# esd_fall_project_rev1.net
KiCad netlist of a schematic drawn in EAGLE
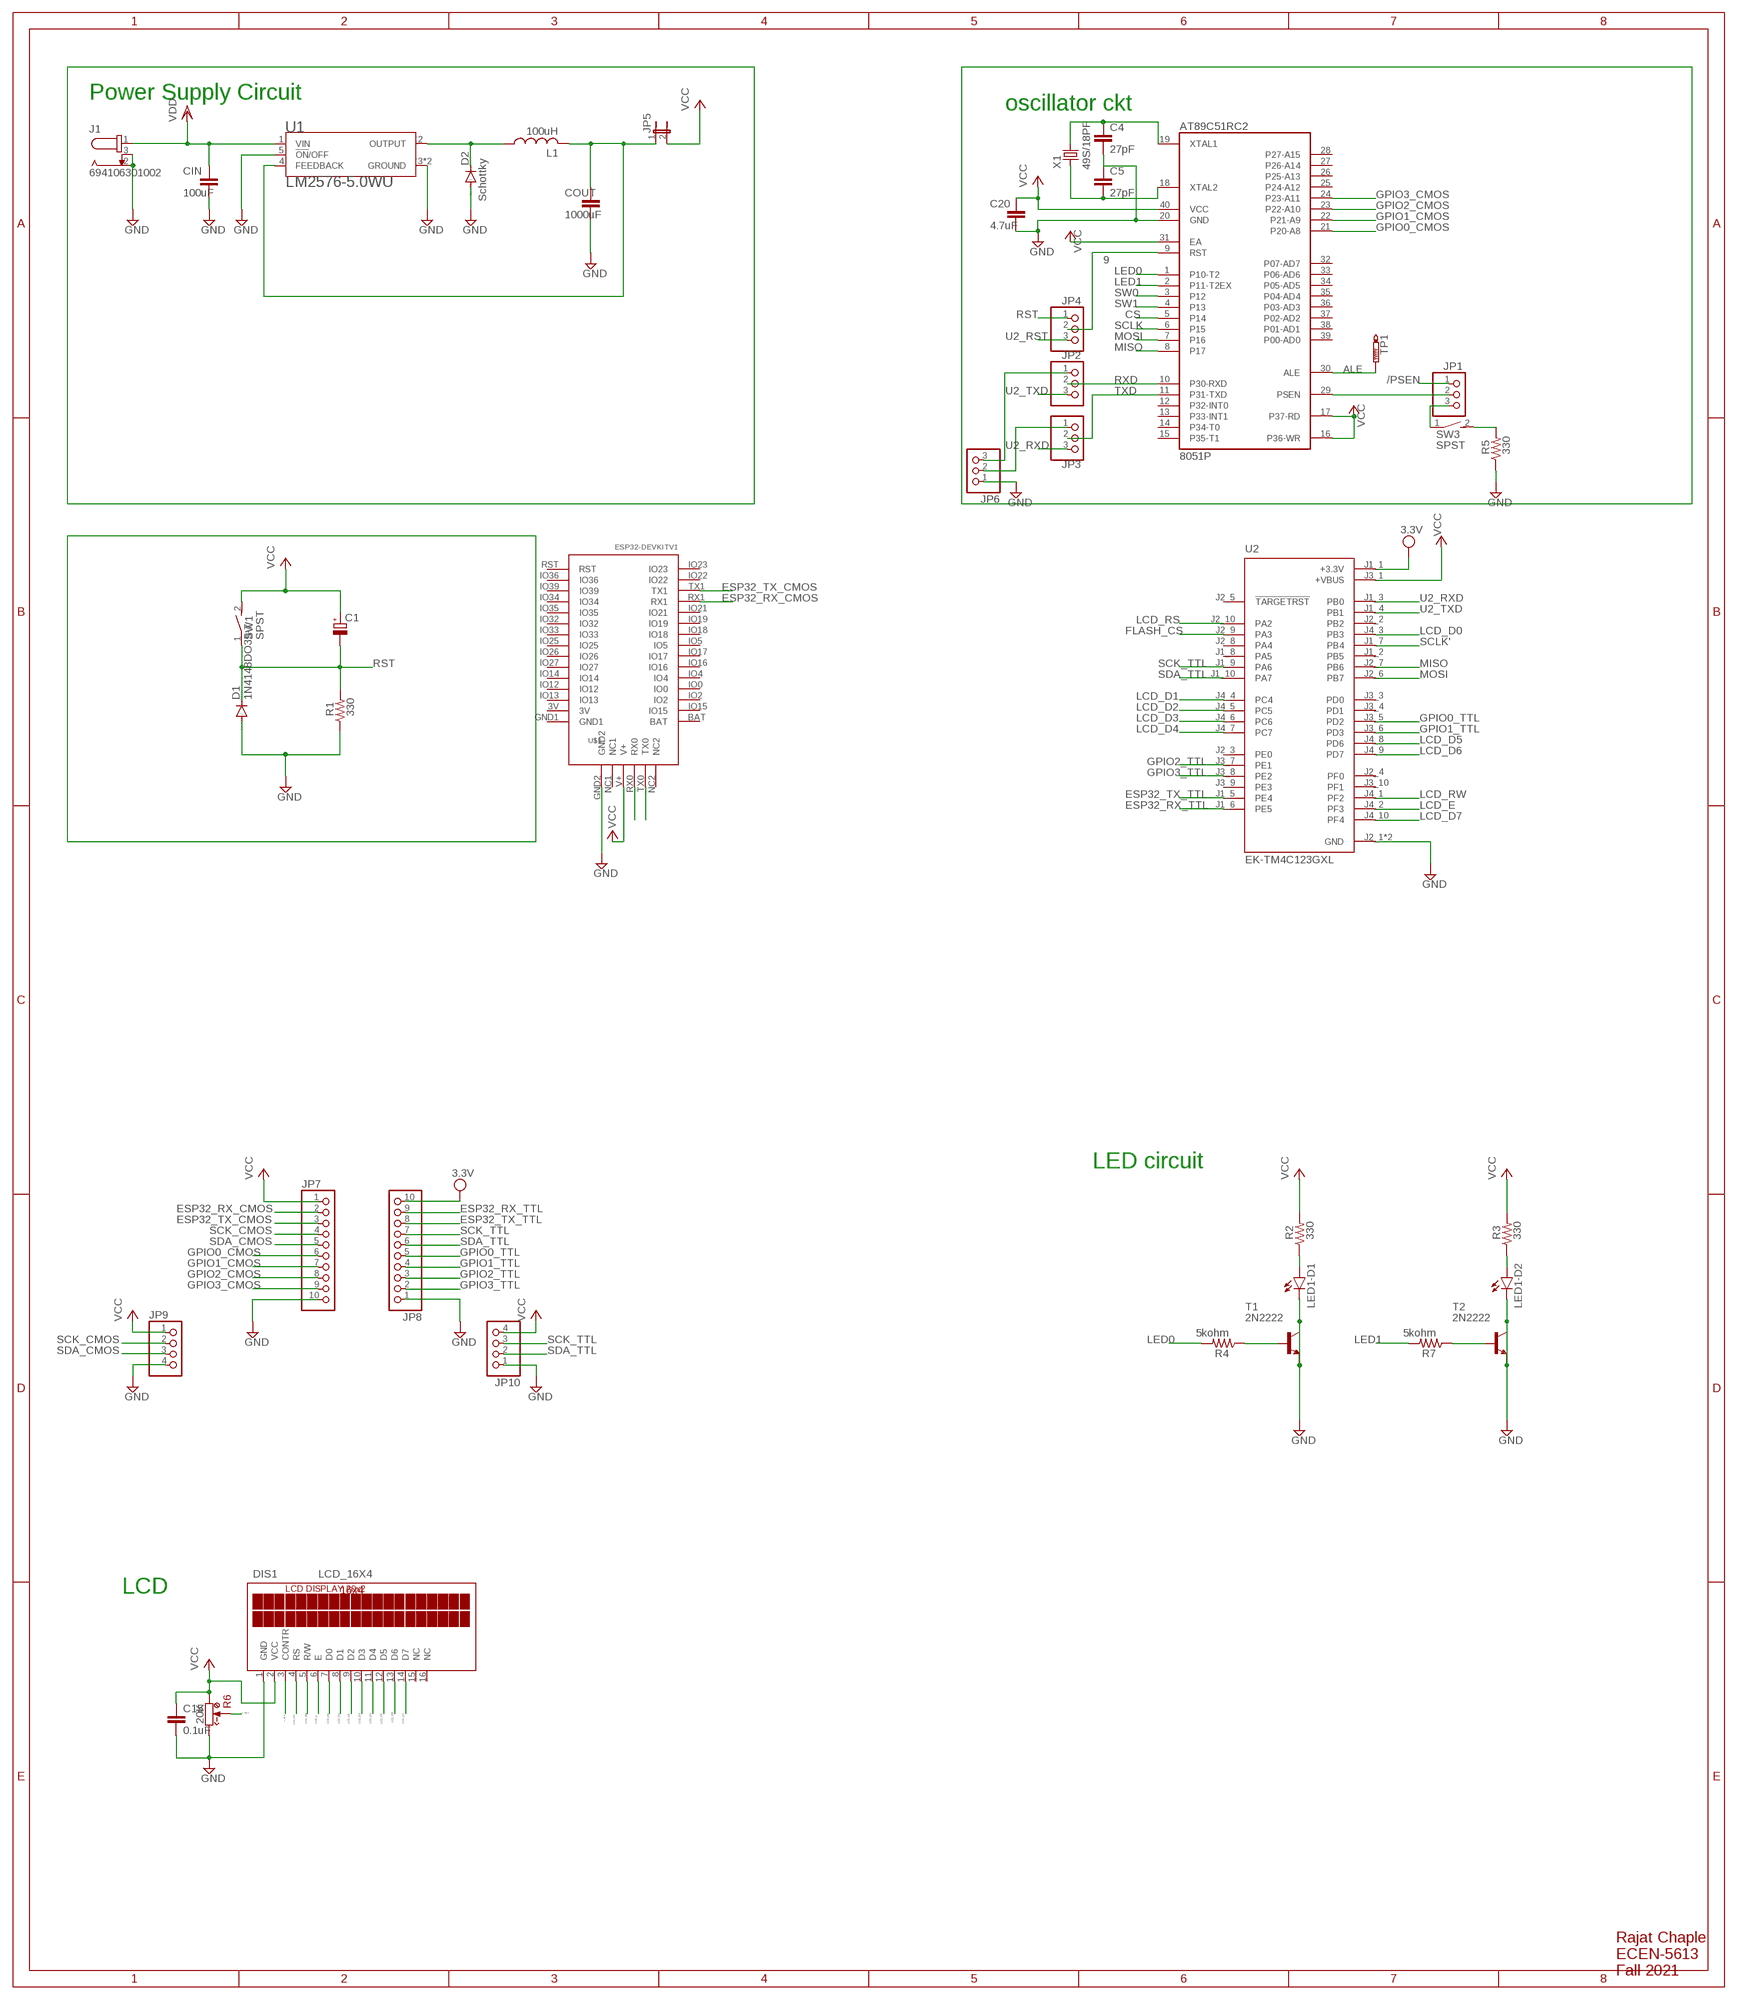
[diagram p0: schematic, sheet 1]

(export (version "E")
  (design (tool "Eeschema 10.0.6"))
  (components
    (comp (ref "AT89C51RC2")
      (value "8051P")
      (footprint "eagle-import:DIL40")
      (libsource (lib "eagle-import") (part "8051P"))
    )
    (comp (ref "C1")
      (value "CPOL-EUE1.8-4")
      (footprint "eagle-import:E1,8-4")
      (libsource (lib "eagle-import") (part "CPOL-EUE1.8-4"))
    )
    (comp (ref "C4")
      (value "27pF")
      (footprint "eagle-import:C2.5-3")
      (libsource (lib "eagle-import") (part "C2,5-3"))
    )
    (comp (ref "C5")
      (value "27pF")
      (footprint "eagle-import:C2.5-3")
      (libsource (lib "eagle-import") (part "C2,5-3"))
    )
    (comp (ref "C15")
      (value "0.1uF")
      (footprint "eagle-import:C2.5-3")
      (libsource (lib "eagle-import") (part "C2,5-3"))
    )
    (comp (ref "C20")
      (value "4.7uF")
      (footprint "eagle-import:C2.5-3")
      (libsource (lib "eagle-import") (part "C2,5-3"))
    )
    (comp (ref "CIN")
      (value "100uF")
      (footprint "eagle-import:C2.5-3")
      (libsource (lib "eagle-import") (part "C2,5-3"))
    )
    (comp (ref "COUT")
      (value "1000uF")
      (footprint "eagle-import:C2.5-3")
      (libsource (lib "eagle-import") (part "C2,5-3"))
    )
    (comp (ref "D1")
      (value "1N4148DO35-7")
      (footprint "eagle-import:DO35-7")
      (libsource (lib "eagle-import") (part "1N4148DO35-7"))
    )
    (comp (ref "D2")
      (value "Schottky")
      (footprint "eagle-import:DO35-7")
      (libsource (lib "eagle-import") (part "1N4148DO35-7"))
    )
    (comp (ref "DIS1")
      (value "LCD_16X4")
      (footprint "eagle-import:TUXGR_20X2")
      (libsource (lib "eagle-import") (part "TUXGR_20X2"))
    )
    (comp (ref "J1")
      (value "694106301002")
      (footprint "eagle-import:694106301002")
      (fields
        (field (name "DIGIKEY_PART_NUMBER") "732-5930-ND")
        (field (name "MANUFACTURER") "Wurth Electronics Inc.")
        (field (name "CREATED_BY") "PCBLayout.com")
      )
      (libsource (lib "eagle-import") (part "694106301002"))
    )
    (comp (ref "JP1")
      (value "PINHD-1X3")
      (footprint "eagle-import:1X03")
      (libsource (lib "eagle-import") (part "PINHD-1X3"))
    )
    (comp (ref "JP2")
      (value "PINHD-1X3")
      (footprint "eagle-import:1X03")
      (libsource (lib "eagle-import") (part "PINHD-1X3"))
    )
    (comp (ref "JP3")
      (value "PINHD-1X3")
      (footprint "eagle-import:1X03")
      (libsource (lib "eagle-import") (part "PINHD-1X3"))
    )
    (comp (ref "JP4")
      (value "PINHD-1X3")
      (footprint "eagle-import:1X03")
      (libsource (lib "eagle-import") (part "PINHD-1X3"))
    )
    (comp (ref "JP5")
      (value "JP1E")
      (footprint "eagle-import:JP1")
      (libsource (lib "eagle-import") (part "JP1E"))
    )
    (comp (ref "JP6")
      (value "PINHD-1X3")
      (footprint "eagle-import:1X03")
      (libsource (lib "eagle-import") (part "PINHD-1X3"))
    )
    (comp (ref "JP7")
      (value "PINHD-1X10")
      (footprint "eagle-import:1X10")
      (libsource (lib "eagle-import") (part "PINHD-1X10"))
    )
    (comp (ref "JP8")
      (value "PINHD-1X10")
      (footprint "eagle-import:1X10")
      (libsource (lib "eagle-import") (part "PINHD-1X10"))
    )
    (comp (ref "JP9")
      (value "PINHD-1X4")
      (footprint "eagle-import:1X04")
      (libsource (lib "eagle-import") (part "PINHD-1X4"))
    )
    (comp (ref "JP10")
      (value "PINHD-1X4")
      (footprint "eagle-import:1X04")
      (libsource (lib "eagle-import") (part "PINHD-1X4"))
    )
    (comp (ref "L1")
      (value "100uH")
      (footprint "eagle-import:0204_5")
      (libsource (lib "eagle-import") (part "L-US0204/5"))
    )
    (comp (ref "LED1-D1")
      (value "LED5MM")
      (footprint "eagle-import:LED5MM")
      (libsource (lib "eagle-import") (part "LED5MM"))
    )
    (comp (ref "LED1-D2")
      (value "LED5MM")
      (footprint "eagle-import:LED5MM")
      (libsource (lib "eagle-import") (part "LED5MM"))
    )
    (comp (ref "R1")
      (value "330")
      (footprint "eagle-import:0204_7")
      (libsource (lib "eagle-import") (part "R-US_0204/7"))
    )
    (comp (ref "R2")
      (value "330")
      (footprint "eagle-import:0204_7")
      (libsource (lib "eagle-import") (part "R-US_0204/7"))
    )
    (comp (ref "R3")
      (value "330")
      (footprint "eagle-import:0204_7")
      (libsource (lib "eagle-import") (part "R-US_0204/7"))
    )
    (comp (ref "R4")
      (value "5kohm")
      (footprint "eagle-import:0204_7")
      (libsource (lib "eagle-import") (part "R-US_0204/7"))
    )
    (comp (ref "R5")
      (value "330")
      (footprint "eagle-import:0204_7")
      (libsource (lib "eagle-import") (part "R-US_0204/7"))
    )
    (comp (ref "R6")
      (value "20K")
      (footprint "eagle-import:64W")
      (libsource (lib "eagle-import") (part "?(64W/Y)100K"))
    )
    (comp (ref "R7")
      (value "5kohm")
      (footprint "eagle-import:0204_7")
      (libsource (lib "eagle-import") (part "R-US_0204/7"))
    )
    (comp (ref "SW1")
      (value "SPST")
      (footprint "eagle-import:DS-01")
      (libsource (lib "eagle-import") (part "DS01E"))
    )
    (comp (ref "SW3")
      (value "SPST")
      (footprint "eagle-import:DS-01")
      (libsource (lib "eagle-import") (part "DS01E"))
    )
    (comp (ref "T1")
      (value "2N2222")
      (footprint "eagle-import:TO18")
      (libsource (lib "eagle-import") (part "2N2222"))
    )
    (comp (ref "T2")
      (value "2N2222")
      (footprint "eagle-import:TO18")
      (libsource (lib "eagle-import") (part "2N2222"))
    )
    (comp (ref "TP1")
      (value "PTR1B2,54")
      (footprint "eagle-import:B2,54")
      (libsource (lib "eagle-import") (part "PTR1B2,54"))
    )
    (comp (ref "U$1")
      (value "ESP32DEVKITV1")
      (footprint "eagle-import:ESP32-DEVKITV1")
      (libsource (lib "eagle-import") (part "ESP32DEVKITV1"))
    )
    (comp (ref "U1")
      (value "LM2576-5.0WU")
      (footprint "eagle-import:DPAK6P170_1524X459L254X81N")
      (fields (field (name "MF") "Microchip") (field (name "MP") "LM2576-5.0WU-TR"))
      (libsource (lib "eagle-import") (part "LM2576-5.0WU"))
    )
    (comp (ref "U2")
      (value "EK-TM4C123GXL")
      (footprint "eagle-import:MODULE_EK-TM4C123GXL")
      (fields (field (name "MF") "Texas Instruments"))
      (libsource (lib "eagle-import") (part "EK-TM4C123GXL"))
    )
    (comp (ref "X1")
      (value "49S/18PF")
      (footprint "eagle-import:XTAL_HC49")
      (fields (field (name "MANUFACTURER") "Xinhunjing ") (field (name "CREATED_BY") "PCBLayout.com"))
      (libsource (lib "eagle-import") (part "49S/18PF"))
    )
  )
  (nets
    (net (code "1") (name "/9") (class "Default")
      (node (ref "AT89C51RC2") (pin "9") (pinfunction "RST_9") (pintype "input"))
      (node (ref "JP4") (pin "2") (pinfunction "2_2") (pintype "passive"))
    )
    (net (code "2") (name "/ALE") (class "Default")
      (node (ref "AT89C51RC2") (pin "30") (pinfunction "ALE_30") (pintype "output"))
      (node (ref "TP1") (pin "TP") (pinfunction "TP_TP") (pintype "input"))
    )
    (net (code "3") (name "/CS") (class "Default")
      (node (ref "AT89C51RC2") (pin "5") (pinfunction "P14_5") (pintype "bidirectional"))
    )
    (net (code "4") (name "/ESP32_RX_CMOS") (class "Default")
      (node (ref "JP7") (pin "2") (pinfunction "2_2") (pintype "passive"))
      (node (ref "U$1") (pin "RX1") (pinfunction "RX1_RX1") (pintype "bidirectional"))
    )
    (net (code "5") (name "/ESP32_RX_TTL") (class "Default")
      (node (ref "JP8") (pin "9") (pinfunction "9_9") (pintype "passive"))
      (node (ref "U2") (pin "J1_6") (pinfunction "PE5_J1_6") (pintype "bidirectional"))
    )
    (net (code "6") (name "/ESP32_TX_CMOS") (class "Default")
      (node (ref "JP7") (pin "3") (pinfunction "3_3") (pintype "passive"))
      (node (ref "U$1") (pin "TX1") (pinfunction "TX1_TX1") (pintype "bidirectional"))
    )
    (net (code "7") (name "/ESP32_TX_TTL") (class "Default")
      (node (ref "JP8") (pin "8") (pinfunction "8_8") (pintype "passive"))
      (node (ref "U2") (pin "J1_5") (pinfunction "PE4_J1_5") (pintype "bidirectional"))
    )
    (net (code "8") (name "/FLASH_CS") (class "Default")
      (node (ref "U2") (pin "J2_9") (pinfunction "PA3_J2_9") (pintype "bidirectional"))
    )
    (net (code "9") (name "/GPIO0_CMOS") (class "Default")
      (node (ref "AT89C51RC2") (pin "21") (pinfunction "P20-A8_21") (pintype "bidirectional"))
      (node (ref "JP7") (pin "6") (pinfunction "6_6") (pintype "passive"))
    )
    (net (code "10") (name "/GPIO0_TTL") (class "Default")
      (node (ref "JP8") (pin "5") (pinfunction "5_5") (pintype "passive"))
      (node (ref "U2") (pin "J3_5") (pinfunction "PD2_J3_5") (pintype "bidirectional"))
    )
    (net (code "11") (name "/GPIO1_CMOS") (class "Default")
      (node (ref "AT89C51RC2") (pin "22") (pinfunction "P21-A9_22") (pintype "bidirectional"))
      (node (ref "JP7") (pin "7") (pinfunction "7_7") (pintype "passive"))
    )
    (net (code "12") (name "/GPIO1_TTL") (class "Default")
      (node (ref "JP8") (pin "4") (pinfunction "4_4") (pintype "passive"))
      (node (ref "U2") (pin "J3_6") (pinfunction "PD3_J3_6") (pintype "bidirectional"))
    )
    (net (code "13") (name "/GPIO2_CMOS") (class "Default")
      (node (ref "AT89C51RC2") (pin "23") (pinfunction "P22-A10_23") (pintype "bidirectional"))
      (node (ref "JP7") (pin "8") (pinfunction "8_8") (pintype "passive"))
    )
    (net (code "14") (name "/GPIO2_TTL") (class "Default")
      (node (ref "JP8") (pin "3") (pinfunction "3_3") (pintype "passive"))
      (node (ref "U2") (pin "J3_7") (pinfunction "PE1_J3_7") (pintype "bidirectional"))
    )
    (net (code "15") (name "/GPIO3_CMOS") (class "Default")
      (node (ref "AT89C51RC2") (pin "24") (pinfunction "P23-A11_24") (pintype "bidirectional"))
      (node (ref "JP7") (pin "9") (pinfunction "9_9") (pintype "passive"))
    )
    (net (code "16") (name "/GPIO3_TTL") (class "Default")
      (node (ref "JP8") (pin "2") (pinfunction "2_2") (pintype "passive"))
      (node (ref "U2") (pin "J3_8") (pinfunction "PE2_J3_8") (pintype "bidirectional"))
    )
    (net (code "17") (name "/LCD_D0") (class "Default")
      (node (ref "DIS1") (pin "7") (pinfunction "D0_7") (pintype "input"))
      (node (ref "U2") (pin "J4_3") (pinfunction "PB3_J4_3") (pintype "bidirectional"))
    )
    (net (code "18") (name "/LCD_D1") (class "Default")
      (node (ref "DIS1") (pin "8") (pinfunction "D1_8") (pintype "input"))
      (node (ref "U2") (pin "J4_4") (pinfunction "PC4_J4_4") (pintype "bidirectional"))
    )
    (net (code "19") (name "/LCD_D2") (class "Default")
      (node (ref "DIS1") (pin "9") (pinfunction "D2_9") (pintype "input"))
      (node (ref "U2") (pin "J4_5") (pinfunction "PC5_J4_5") (pintype "bidirectional"))
    )
    (net (code "20") (name "/LCD_D3") (class "Default")
      (node (ref "DIS1") (pin "10") (pinfunction "D3_10") (pintype "input"))
      (node (ref "U2") (pin "J4_6") (pinfunction "PC6_J4_6") (pintype "bidirectional"))
    )
    (net (code "21") (name "/LCD_D4") (class "Default")
      (node (ref "DIS1") (pin "11") (pinfunction "D4_11") (pintype "input"))
      (node (ref "U2") (pin "J4_7") (pinfunction "PC7_J4_7") (pintype "bidirectional"))
    )
    (net (code "22") (name "/LCD_D5") (class "Default")
      (node (ref "DIS1") (pin "12") (pinfunction "D5_12") (pintype "input"))
      (node (ref "U2") (pin "J4_8") (pinfunction "PD6_J4_8") (pintype "bidirectional"))
    )
    (net (code "23") (name "/LCD_D6") (class "Default")
      (node (ref "DIS1") (pin "13") (pinfunction "D6_13") (pintype "input"))
      (node (ref "U2") (pin "J4_9") (pinfunction "PD7_J4_9") (pintype "bidirectional"))
    )
    (net (code "24") (name "/LCD_D7") (class "Default")
      (node (ref "DIS1") (pin "14") (pinfunction "D7_14") (pintype "input"))
      (node (ref "U2") (pin "J4_10") (pinfunction "PF4_J4_10") (pintype "bidirectional"))
    )
    (net (code "25") (name "/LCD_E") (class "Default")
      (node (ref "DIS1") (pin "6") (pinfunction "E_6") (pintype "input"))
      (node (ref "U2") (pin "J4_2") (pinfunction "PF3_J4_2") (pintype "bidirectional"))
    )
    (net (code "26") (name "/LCD_RS") (class "Default")
      (node (ref "DIS1") (pin "4") (pinfunction "RS_4") (pintype "input"))
      (node (ref "U2") (pin "J2_10") (pinfunction "PA2_J2_10") (pintype "bidirectional"))
    )
    (net (code "27") (name "/LCD_RW") (class "Default")
      (node (ref "DIS1") (pin "5") (pinfunction "R/W_5") (pintype "input"))
      (node (ref "U2") (pin "J4_1") (pinfunction "PF2_J4_1") (pintype "bidirectional"))
    )
    (net (code "28") (name "/LED0") (class "Default")
      (node (ref "AT89C51RC2") (pin "1") (pinfunction "P10-T2_1") (pintype "bidirectional"))
      (node (ref "R4") (pin "2") (pinfunction "2_2") (pintype "passive"))
    )
    (net (code "29") (name "/LED1") (class "Default")
      (node (ref "AT89C51RC2") (pin "2") (pinfunction "P11-T2EX_2") (pintype "bidirectional"))
      (node (ref "R7") (pin "2") (pinfunction "2_2") (pintype "passive"))
    )
    (net (code "30") (name "/MISO") (class "Default")
      (node (ref "AT89C51RC2") (pin "8") (pinfunction "P17_8") (pintype "bidirectional"))
      (node (ref "U2") (pin "J2_7") (pinfunction "PB6_J2_7") (pintype "bidirectional"))
    )
    (net (code "31") (name "/MOSI") (class "Default")
      (node (ref "AT89C51RC2") (pin "7") (pinfunction "P16_7") (pintype "bidirectional"))
      (node (ref "U2") (pin "J2_6") (pinfunction "PB7_J2_6") (pintype "bidirectional"))
    )
    (net (code "32") (name "/RST") (class "Default")
      (node (ref "C1") (pin "-") (pinfunction "-_-") (pintype "passive"))
      (node (ref "D1") (pin "C") (pinfunction "C_C") (pintype "passive"))
      (node (ref "JP4") (pin "1") (pinfunction "1_1") (pintype "passive"))
      (node (ref "R1") (pin "2") (pinfunction "2_2") (pintype "passive"))
      (node (ref "SW1") (pin "1") (pinfunction "1_1") (pintype "passive"))
    )
    (net (code "33") (name "/RXD") (class "Default")
      (node (ref "AT89C51RC2") (pin "10") (pinfunction "P30-RXD_10") (pintype "bidirectional"))
      (node (ref "JP2") (pin "2") (pinfunction "2_2") (pintype "passive"))
    )
    (net (code "34") (name "/SCK_CMOS") (class "Default")
      (node (ref "JP7") (pin "4") (pinfunction "4_4") (pintype "passive"))
      (node (ref "JP9") (pin "2") (pinfunction "2_2") (pintype "passive"))
    )
    (net (code "35") (name "/SCK_TTL") (class "Default")
      (node (ref "JP10") (pin "3") (pinfunction "3_3") (pintype "passive"))
      (node (ref "JP8") (pin "7") (pinfunction "7_7") (pintype "passive"))
      (node (ref "U2") (pin "J1_9") (pinfunction "PA6_J1_9") (pintype "bidirectional"))
    )
    (net (code "36") (name "/SCLK") (class "Default")
      (node (ref "AT89C51RC2") (pin "6") (pinfunction "P15_6") (pintype "bidirectional"))
    )
    (net (code "37") (name "/SCLK'") (class "Default")
      (node (ref "U2") (pin "J1_7") (pinfunction "PB4_J1_7") (pintype "bidirectional"))
    )
    (net (code "38") (name "/SDA_CMOS") (class "Default")
      (node (ref "JP7") (pin "5") (pinfunction "5_5") (pintype "passive"))
      (node (ref "JP9") (pin "3") (pinfunction "3_3") (pintype "passive"))
    )
    (net (code "39") (name "/SDA_TTL") (class "Default")
      (node (ref "JP10") (pin "2") (pinfunction "2_2") (pintype "passive"))
      (node (ref "JP8") (pin "6") (pinfunction "6_6") (pintype "passive"))
      (node (ref "U2") (pin "J1_10") (pinfunction "PA7_J1_10") (pintype "bidirectional"))
    )
    (net (code "40") (name "/SW0") (class "Default")
      (node (ref "AT89C51RC2") (pin "3") (pinfunction "P12_3") (pintype "bidirectional"))
    )
    (net (code "41") (name "/SW1") (class "Default")
      (node (ref "AT89C51RC2") (pin "4") (pinfunction "P13_4") (pintype "bidirectional"))
    )
    (net (code "42") (name "/TXD") (class "Default")
      (node (ref "AT89C51RC2") (pin "11") (pinfunction "P31-TXD_11") (pintype "bidirectional"))
      (node (ref "JP3") (pin "2") (pinfunction "2_2") (pintype "passive"))
    )
    (net (code "43") (name "/U2_RST") (class "Default")
      (node (ref "JP4") (pin "3") (pinfunction "3_3") (pintype "passive"))
    )
    (net (code "44") (name "/U2_RXD") (class "Default")
      (node (ref "JP3") (pin "3") (pinfunction "3_3") (pintype "passive"))
      (node (ref "U2") (pin "J1_3") (pinfunction "PB0_J1_3") (pintype "bidirectional"))
    )
    (net (code "45") (name "/U2_TXD") (class "Default")
      (node (ref "JP2") (pin "3") (pinfunction "3_3") (pintype "passive"))
      (node (ref "U2") (pin "J1_4") (pinfunction "PB1_J1_4") (pintype "bidirectional"))
    )
    (net (code "46") (name "/V_RES") (class "Default")
      (node (ref "DIS1") (pin "3") (pinfunction "CONTR_3") (pintype "input"))
    )
    (net (code "47") (name "/{slash}PSEN") (class "Default")
      (node (ref "JP1") (pin "1") (pinfunction "1_1") (pintype "passive"))
    )
    (net (code "48") (name "3.3V") (class "Default")
      (node (ref "CIN") (pin "1") (pinfunction "1_1") (pintype "passive"))
      (node (ref "J1") (pin "1") (pinfunction "1_1") (pintype "passive"))
      (node (ref "JP8") (pin "10") (pinfunction "10_10") (pintype "passive"))
      (node (ref "U1") (pin "1") (pinfunction "VIN_1") (pintype "input"))
      (node (ref "U2") (pin "J1_1") (pinfunction "+3.3V_J1_1") (pintype "power_in"))
    )
    (net (code "49") (name "GND") (class "Default")
      (node (ref "AT89C51RC2") (pin "20") (pinfunction "GND_20") (pintype "power_in"))
      (node (ref "C15") (pin "2") (pinfunction "2_2") (pintype "passive"))
      (node (ref "C20") (pin "2") (pinfunction "2_2") (pintype "passive"))
      (node (ref "C4") (pin "2") (pinfunction "2_2") (pintype "passive"))
      (node (ref "C5") (pin "1") (pinfunction "1_1") (pintype "passive"))
      (node (ref "CIN") (pin "2") (pinfunction "2_2") (pintype "passive"))
      (node (ref "COUT") (pin "2") (pinfunction "2_2") (pintype "passive"))
      (node (ref "D1") (pin "A") (pinfunction "A_A") (pintype "passive"))
      (node (ref "D2") (pin "A") (pinfunction "A_A") (pintype "passive"))
      (node (ref "DIS1") (pin "1") (pinfunction "GND_1") (pintype "power_in"))
      (node (ref "J1") (pin "2") (pinfunction "2_2") (pintype "passive"))
      (node (ref "J1") (pin "3") (pinfunction "3_3") (pintype "passive"))
      (node (ref "JP10") (pin "1") (pinfunction "1_1") (pintype "passive"))
      (node (ref "JP6") (pin "1") (pinfunction "1_1") (pintype "passive"))
      (node (ref "JP7") (pin "10") (pinfunction "10_10") (pintype "passive"))
      (node (ref "JP8") (pin "1") (pinfunction "1_1") (pintype "passive"))
      (node (ref "JP9") (pin "4") (pinfunction "4_4") (pintype "passive"))
      (node (ref "LED1-D1") (pin "K") (pinfunction "C_K") (pintype "passive"))
      (node (ref "LED1-D2") (pin "K") (pinfunction "C_K") (pintype "passive"))
      (node (ref "R1") (pin "1") (pinfunction "1_1") (pintype "passive"))
      (node (ref "R5") (pin "1") (pinfunction "1_1") (pintype "passive"))
      (node (ref "R6") (pin "3") (pinfunction "CW_3") (pintype "passive"))
      (node (ref "T1") (pin "1") (pinfunction "E_1") (pintype "passive"))
      (node (ref "T1") (pin "3") (pinfunction "C_3") (pintype "passive"))
      (node (ref "T2") (pin "1") (pinfunction "E_1") (pintype "passive"))
      (node (ref "T2") (pin "3") (pinfunction "C_3") (pintype "passive"))
      (node (ref "U$1") (pin "GND2") (pinfunction "GND2_GND2") (pintype "bidirectional"))
      (node (ref "U1") (pin "3") (pinfunction "GROUND_3") (pintype "power_in"))
      (node (ref "U1") (pin "5") (pinfunction "~{ON}/OFF_5") (pintype "input"))
      (node (ref "U1") (pin "6") (pinfunction "GROUND_6") (pintype "power_in"))
      (node (ref "U2") (pin "J2_1") (pinfunction "GND_J2_1") (pintype "power_in"))
      (node (ref "U2") (pin "J3_2") (pinfunction "GND_J3_2") (pintype "power_in"))
    )
    (net (code "50") (name "Net-(AT89C51RC2-PSEN)") (class "Default")
      (node (ref "AT89C51RC2") (pin "29") (pinfunction "PSEN_29") (pintype "output"))
      (node (ref "JP1") (pin "2") (pinfunction "2_2") (pintype "passive"))
    )
    (net (code "51") (name "Net-(AT89C51RC2-XTAL1)") (class "Default")
      (node (ref "AT89C51RC2") (pin "19") (pinfunction "XTAL1_19") (pintype "input"))
      (node (ref "C4") (pin "1") (pinfunction "1_1") (pintype "passive"))
      (node (ref "X1") (pin "2") (pinfunction "2_2") (pintype "passive"))
    )
    (net (code "52") (name "Net-(AT89C51RC2-XTAL2)") (class "Default")
      (node (ref "AT89C51RC2") (pin "18") (pinfunction "XTAL2_18") (pintype "input"))
      (node (ref "C5") (pin "2") (pinfunction "2_2") (pintype "passive"))
      (node (ref "X1") (pin "1") (pinfunction "1_1") (pintype "passive"))
    )
    (net (code "53") (name "Net-(JP1-Pad3)") (class "Default")
      (node (ref "JP1") (pin "3") (pinfunction "3_3") (pintype "passive"))
      (node (ref "SW3") (pin "1") (pinfunction "1_1") (pintype "passive"))
    )
    (net (code "54") (name "Net-(JP2-Pad1)") (class "Default")
      (node (ref "JP2") (pin "1") (pinfunction "1_1") (pintype "passive"))
      (node (ref "JP6") (pin "3") (pinfunction "3_3") (pintype "passive"))
    )
    (net (code "55") (name "Net-(JP3-Pad1)") (class "Default")
      (node (ref "JP3") (pin "1") (pinfunction "1_1") (pintype "passive"))
      (node (ref "JP6") (pin "2") (pinfunction "2_2") (pintype "passive"))
    )
    (net (code "56") (name "Net-(LED1-D1-PadA)") (class "Default")
      (node (ref "LED1-D1") (pin "A") (pinfunction "A_A") (pintype "passive"))
      (node (ref "R2") (pin "1") (pinfunction "1_1") (pintype "passive"))
    )
    (net (code "57") (name "Net-(LED1-D2-PadA)") (class "Default")
      (node (ref "LED1-D2") (pin "A") (pinfunction "A_A") (pintype "passive"))
      (node (ref "R3") (pin "1") (pinfunction "1_1") (pintype "passive"))
    )
    (net (code "58") (name "Net-(R5-Pad2)") (class "Default")
      (node (ref "R5") (pin "2") (pinfunction "2_2") (pintype "passive"))
      (node (ref "SW3") (pin "2") (pinfunction "2_2") (pintype "passive"))
    )
    (net (code "59") (name "Net-(R6-W-PadS)") (class "Default")
      (node (ref "R6") (pin "S") (pinfunction "W_S") (pintype "passive"))
      (node (ref "R6") (pin "S@1") (pinfunction "W_S@1") (pintype "passive"))
    )
    (net (code "60") (name "Net-(T1-B)") (class "Default")
      (node (ref "R4") (pin "1") (pinfunction "1_1") (pintype "passive"))
      (node (ref "T1") (pin "2") (pinfunction "B_2") (pintype "passive"))
    )
    (net (code "61") (name "Net-(T2-B)") (class "Default")
      (node (ref "R7") (pin "1") (pinfunction "1_1") (pintype "passive"))
      (node (ref "T2") (pin "2") (pinfunction "B_2") (pintype "passive"))
    )
    (net (code "62") (name "Net-(U1-FEEDBACK)") (class "Default")
      (node (ref "COUT") (pin "1") (pinfunction "1_1") (pintype "passive"))
      (node (ref "JP5") (pin "1") (pinfunction "1_1") (pintype "passive"))
      (node (ref "L1") (pin "2") (pinfunction "2_2") (pintype "passive"))
      (node (ref "U1") (pin "4") (pinfunction "FEEDBACK_4") (pintype "bidirectional"))
    )
    (net (code "63") (name "Net-(U1-OUTPUT)") (class "Default")
      (node (ref "D2") (pin "C") (pinfunction "C_C") (pintype "passive"))
      (node (ref "L1") (pin "1") (pinfunction "1_1") (pintype "passive"))
      (node (ref "U1") (pin "2") (pinfunction "OUTPUT_2") (pintype "output"))
    )
    (net (code "64") (name "VCC") (class "Default")
      (node (ref "AT89C51RC2") (pin "16") (pinfunction "P36-WR_16") (pintype "bidirectional"))
      (node (ref "AT89C51RC2") (pin "17") (pinfunction "P37-RD_17") (pintype "bidirectional"))
      (node (ref "AT89C51RC2") (pin "31") (pinfunction "EA_31") (pintype "input"))
      (node (ref "AT89C51RC2") (pin "40") (pinfunction "VCC_40") (pintype "power_in"))
      (node (ref "C1") (pin "+") (pinfunction "+_+") (pintype "passive"))
      (node (ref "C15") (pin "1") (pinfunction "1_1") (pintype "passive"))
      (node (ref "C20") (pin "1") (pinfunction "1_1") (pintype "passive"))
      (node (ref "DIS1") (pin "2") (pinfunction "VCC_2") (pintype "power_in"))
      (node (ref "JP10") (pin "4") (pinfunction "4_4") (pintype "passive"))
      (node (ref "JP5") (pin "2") (pinfunction "2_2") (pintype "passive"))
      (node (ref "JP7") (pin "1") (pinfunction "1_1") (pintype "passive"))
      (node (ref "JP9") (pin "1") (pinfunction "1_1") (pintype "passive"))
      (node (ref "R2") (pin "2") (pinfunction "2_2") (pintype "passive"))
      (node (ref "R3") (pin "2") (pinfunction "2_2") (pintype "passive"))
      (node (ref "R6") (pin "1") (pinfunction "CCW_1") (pintype "passive"))
      (node (ref "SW1") (pin "2") (pinfunction "2_2") (pintype "passive"))
      (node (ref "U$1") (pin "V+") (pinfunction "V+_V+") (pintype "bidirectional"))
      (node (ref "U2") (pin "J3_1") (pinfunction "+VBUS_J3_1") (pintype "power_in"))
    )
    (net (code "65") (name "unconnected-(AT89C51RC2-P00-AD0-Pad39)") (class "Default")
      (node (ref "AT89C51RC2") (pin "39") (pinfunction "P00-AD0_39") (pintype "bidirectional"))
    )
    (net (code "66") (name "unconnected-(AT89C51RC2-P01-AD1-Pad38)") (class "Default")
      (node (ref "AT89C51RC2") (pin "38") (pinfunction "P01-AD1_38") (pintype "bidirectional"))
    )
    (net (code "67") (name "unconnected-(AT89C51RC2-P02-AD2-Pad37)") (class "Default")
      (node (ref "AT89C51RC2") (pin "37") (pinfunction "P02-AD2_37") (pintype "bidirectional"))
    )
    (net (code "68") (name "unconnected-(AT89C51RC2-P03-AD3-Pad36)") (class "Default")
      (node (ref "AT89C51RC2") (pin "36") (pinfunction "P03-AD3_36") (pintype "bidirectional"))
    )
    (net (code "69") (name "unconnected-(AT89C51RC2-P04-AD4-Pad35)") (class "Default")
      (node (ref "AT89C51RC2") (pin "35") (pinfunction "P04-AD4_35") (pintype "bidirectional"))
    )
    (net (code "70") (name "unconnected-(AT89C51RC2-P05-AD5-Pad34)") (class "Default")
      (node (ref "AT89C51RC2") (pin "34") (pinfunction "P05-AD5_34") (pintype "bidirectional"))
    )
    (net (code "71") (name "unconnected-(AT89C51RC2-P06-AD6-Pad33)") (class "Default")
      (node (ref "AT89C51RC2") (pin "33") (pinfunction "P06-AD6_33") (pintype "bidirectional"))
    )
    (net (code "72") (name "unconnected-(AT89C51RC2-P07-AD7-Pad32)") (class "Default")
      (node (ref "AT89C51RC2") (pin "32") (pinfunction "P07-AD7_32") (pintype "bidirectional"))
    )
    (net (code "73") (name "unconnected-(AT89C51RC2-P24-A12-Pad25)") (class "Default")
      (node (ref "AT89C51RC2") (pin "25") (pinfunction "P24-A12_25") (pintype "bidirectional"))
    )
    (net (code "74") (name "unconnected-(AT89C51RC2-P25-A13-Pad26)") (class "Default")
      (node (ref "AT89C51RC2") (pin "26") (pinfunction "P25-A13_26") (pintype "bidirectional"))
    )
    (net (code "75") (name "unconnected-(AT89C51RC2-P26-A14-Pad27)") (class "Default")
      (node (ref "AT89C51RC2") (pin "27") (pinfunction "P26-A14_27") (pintype "bidirectional"))
    )
    (net (code "76") (name "unconnected-(AT89C51RC2-P27-A15-Pad28)") (class "Default")
      (node (ref "AT89C51RC2") (pin "28") (pinfunction "P27-A15_28") (pintype "bidirectional"))
    )
    (net (code "77") (name "unconnected-(AT89C51RC2-P32-INT0-Pad12)") (class "Default")
      (node (ref "AT89C51RC2") (pin "12") (pinfunction "P32-INT0_12") (pintype "bidirectional"))
    )
    (net (code "78") (name "unconnected-(AT89C51RC2-P33-INT1-Pad13)") (class "Default")
      (node (ref "AT89C51RC2") (pin "13") (pinfunction "P33-INT1_13") (pintype "bidirectional"))
    )
    (net (code "79") (name "unconnected-(AT89C51RC2-P34-T0-Pad14)") (class "Default")
      (node (ref "AT89C51RC2") (pin "14") (pinfunction "P34-T0_14") (pintype "bidirectional"))
    )
    (net (code "80") (name "unconnected-(AT89C51RC2-P35-T1-Pad15)") (class "Default")
      (node (ref "AT89C51RC2") (pin "15") (pinfunction "P35-T1_15") (pintype "bidirectional"))
    )
    (net (code "81") (name "unconnected-(DIS1-NC-Pad15)") (class "Default")
      (node (ref "DIS1") (pin "15") (pinfunction "NC_15") (pintype "no_connect"))
    )
    (net (code "82") (name "unconnected-(DIS1-NC-Pad16)") (class "Default")
      (node (ref "DIS1") (pin "16") (pinfunction "NC_16") (pintype "no_connect"))
    )
    (net (code "83") (name "unconnected-(U$1-Pad3V)") (class "Default")
      (node (ref "U$1") (pin "3V") (pinfunction "3V_3V") (pintype "bidirectional"))
    )
    (net (code "84") (name "unconnected-(U$1-PadBAT)") (class "Default")
      (node (ref "U$1") (pin "BAT") (pinfunction "BAT_BAT") (pintype "bidirectional"))
    )
    (net (code "85") (name "unconnected-(U$1-PadGND1)") (class "Default")
      (node (ref "U$1") (pin "GND1") (pinfunction "GND1_GND1") (pintype "bidirectional"))
    )
    (net (code "86") (name "unconnected-(U$1-PadIO0)") (class "Default")
      (node (ref "U$1") (pin "IO0") (pinfunction "IO0_IO0") (pintype "bidirectional"))
    )
    (net (code "87") (name "unconnected-(U$1-PadIO2)") (class "Default")
      (node (ref "U$1") (pin "IO2") (pinfunction "IO2_IO2") (pintype "bidirectional"))
    )
    (net (code "88") (name "unconnected-(U$1-PadIO4)") (class "Default")
      (node (ref "U$1") (pin "IO4") (pinfunction "IO4_IO4") (pintype "bidirectional"))
    )
    (net (code "89") (name "unconnected-(U$1-PadIO5)") (class "Default")
      (node (ref "U$1") (pin "IO5") (pinfunction "IO5_IO5") (pintype "bidirectional"))
    )
    (net (code "90") (name "unconnected-(U$1-PadIO12)") (class "Default")
      (node (ref "U$1") (pin "IO12") (pinfunction "IO12_IO12") (pintype "bidirectional"))
    )
    (net (code "91") (name "unconnected-(U$1-PadIO13)") (class "Default")
      (node (ref "U$1") (pin "IO13") (pinfunction "IO13_IO13") (pintype "bidirectional"))
    )
    (net (code "92") (name "unconnected-(U$1-PadIO14)") (class "Default")
      (node (ref "U$1") (pin "IO14") (pinfunction "IO14_IO14") (pintype "bidirectional"))
    )
    (net (code "93") (name "unconnected-(U$1-PadIO15)") (class "Default")
      (node (ref "U$1") (pin "IO15") (pinfunction "IO15_IO15") (pintype "bidirectional"))
    )
    (net (code "94") (name "unconnected-(U$1-PadIO16)") (class "Default")
      (node (ref "U$1") (pin "IO16") (pinfunction "IO16_IO16") (pintype "bidirectional"))
    )
    (net (code "95") (name "unconnected-(U$1-PadIO17)") (class "Default")
      (node (ref "U$1") (pin "IO17") (pinfunction "IO17_IO17") (pintype "bidirectional"))
    )
    (net (code "96") (name "unconnected-(U$1-PadIO18)") (class "Default")
      (node (ref "U$1") (pin "IO18") (pinfunction "IO18_IO18") (pintype "bidirectional"))
    )
    (net (code "97") (name "unconnected-(U$1-PadIO19)") (class "Default")
      (node (ref "U$1") (pin "IO19") (pinfunction "IO19_IO19") (pintype "bidirectional"))
    )
    (net (code "98") (name "unconnected-(U$1-PadIO21)") (class "Default")
      (node (ref "U$1") (pin "IO21") (pinfunction "IO21_IO21") (pintype "bidirectional"))
    )
    (net (code "99") (name "unconnected-(U$1-PadIO22)") (class "Default")
      (node (ref "U$1") (pin "IO22") (pinfunction "IO22_IO22") (pintype "bidirectional"))
    )
    (net (code "100") (name "unconnected-(U$1-PadIO23)") (class "Default")
      (node (ref "U$1") (pin "IO23") (pinfunction "IO23_IO23") (pintype "bidirectional"))
    )
    (net (code "101") (name "unconnected-(U$1-PadIO25)") (class "Default")
      (node (ref "U$1") (pin "IO25") (pinfunction "IO25_IO25") (pintype "bidirectional"))
    )
    (net (code "102") (name "unconnected-(U$1-PadIO26)") (class "Default")
      (node (ref "U$1") (pin "IO26") (pinfunction "IO26_IO26") (pintype "bidirectional"))
    )
    (net (code "103") (name "unconnected-(U$1-PadIO27)") (class "Default")
      (node (ref "U$1") (pin "IO27") (pinfunction "IO27_IO27") (pintype "bidirectional"))
    )
    (net (code "104") (name "unconnected-(U$1-PadIO32)") (class "Default")
      (node (ref "U$1") (pin "IO32") (pinfunction "IO32_IO32") (pintype "bidirectional"))
    )
    (net (code "105") (name "unconnected-(U$1-PadIO33)") (class "Default")
      (node (ref "U$1") (pin "IO33") (pinfunction "IO33_IO33") (pintype "bidirectional"))
    )
    (net (code "106") (name "unconnected-(U$1-PadIO34)") (class "Default")
      (node (ref "U$1") (pin "IO34") (pinfunction "IO34_IO34") (pintype "bidirectional"))
    )
    (net (code "107") (name "unconnected-(U$1-PadIO35)") (class "Default")
      (node (ref "U$1") (pin "IO35") (pinfunction "IO35_IO35") (pintype "bidirectional"))
    )
    (net (code "108") (name "unconnected-(U$1-PadIO36)") (class "Default")
      (node (ref "U$1") (pin "IO36") (pinfunction "IO36_IO36") (pintype "bidirectional"))
    )
    (net (code "109") (name "unconnected-(U$1-PadIO39)") (class "Default")
      (node (ref "U$1") (pin "IO39") (pinfunction "IO39_IO39") (pintype "bidirectional"))
    )
    (net (code "110") (name "unconnected-(U$1-PadNC1)") (class "Default")
      (node (ref "U$1") (pin "NC1") (pinfunction "NC1_NC1") (pintype "bidirectional"))
    )
    (net (code "111") (name "unconnected-(U$1-PadNC2)") (class "Default")
      (node (ref "U$1") (pin "NC2") (pinfunction "NC2_NC2") (pintype "bidirectional"))
    )
    (net (code "112") (name "unconnected-(U$1-PadRST)") (class "Default")
      (node (ref "U$1") (pin "RST") (pinfunction "RST_RST") (pintype "bidirectional"))
    )
    (net (code "113") (name "unconnected-(U$1-PadRX0)") (class "Default")
      (node (ref "U$1") (pin "RX0") (pinfunction "RX0_RX0") (pintype "bidirectional"))
    )
    (net (code "114") (name "unconnected-(U$1-PadTX0)") (class "Default")
      (node (ref "U$1") (pin "TX0") (pinfunction "TX0_TX0") (pintype "bidirectional"))
    )
    (net (code "115") (name "unconnected-(U2-PA4-PadJ2_8)") (class "Default")
      (node (ref "U2") (pin "J2_8") (pinfunction "PA4_J2_8") (pintype "bidirectional"))
    )
    (net (code "116") (name "unconnected-(U2-PA5-PadJ1_8)") (class "Default")
      (node (ref "U2") (pin "J1_8") (pinfunction "PA5_J1_8") (pintype "bidirectional"))
    )
    (net (code "117") (name "unconnected-(U2-PB2-PadJ2_2)") (class "Default")
      (node (ref "U2") (pin "J2_2") (pinfunction "PB2_J2_2") (pintype "bidirectional"))
    )
    (net (code "118") (name "unconnected-(U2-PB5-PadJ1_2)") (class "Default")
      (node (ref "U2") (pin "J1_2") (pinfunction "PB5_J1_2") (pintype "bidirectional"))
    )
    (net (code "119") (name "unconnected-(U2-PD0-PadJ3_3)") (class "Default")
      (node (ref "U2") (pin "J3_3") (pinfunction "PD0_J3_3") (pintype "bidirectional"))
    )
    (net (code "120") (name "unconnected-(U2-PD1-PadJ3_4)") (class "Default")
      (node (ref "U2") (pin "J3_4") (pinfunction "PD1_J3_4") (pintype "bidirectional"))
    )
    (net (code "121") (name "unconnected-(U2-PE0-PadJ2_3)") (class "Default")
      (node (ref "U2") (pin "J2_3") (pinfunction "PE0_J2_3") (pintype "bidirectional"))
    )
    (net (code "122") (name "unconnected-(U2-PE3-PadJ3_9)") (class "Default")
      (node (ref "U2") (pin "J3_9") (pinfunction "PE3_J3_9") (pintype "bidirectional"))
    )
    (net (code "123") (name "unconnected-(U2-PF0-PadJ2_4)") (class "Default")
      (node (ref "U2") (pin "J2_4") (pinfunction "PF0_J2_4") (pintype "bidirectional"))
    )
    (net (code "124") (name "unconnected-(U2-PF1-PadJ3_10)") (class "Default")
      (node (ref "U2") (pin "J3_10") (pinfunction "PF1_J3_10") (pintype "bidirectional"))
    )
    (net (code "125") (name "unconnected-(U2-~{TARGETRST}-PadJ2_5)") (class "Default")
      (node (ref "U2") (pin "J2_5") (pinfunction "~{TARGETRST}_J2_5") (pintype "input"))
    )
  )
)
